# USB_Codec.net
KiCad netlist of a schematic drawn in EAGLE
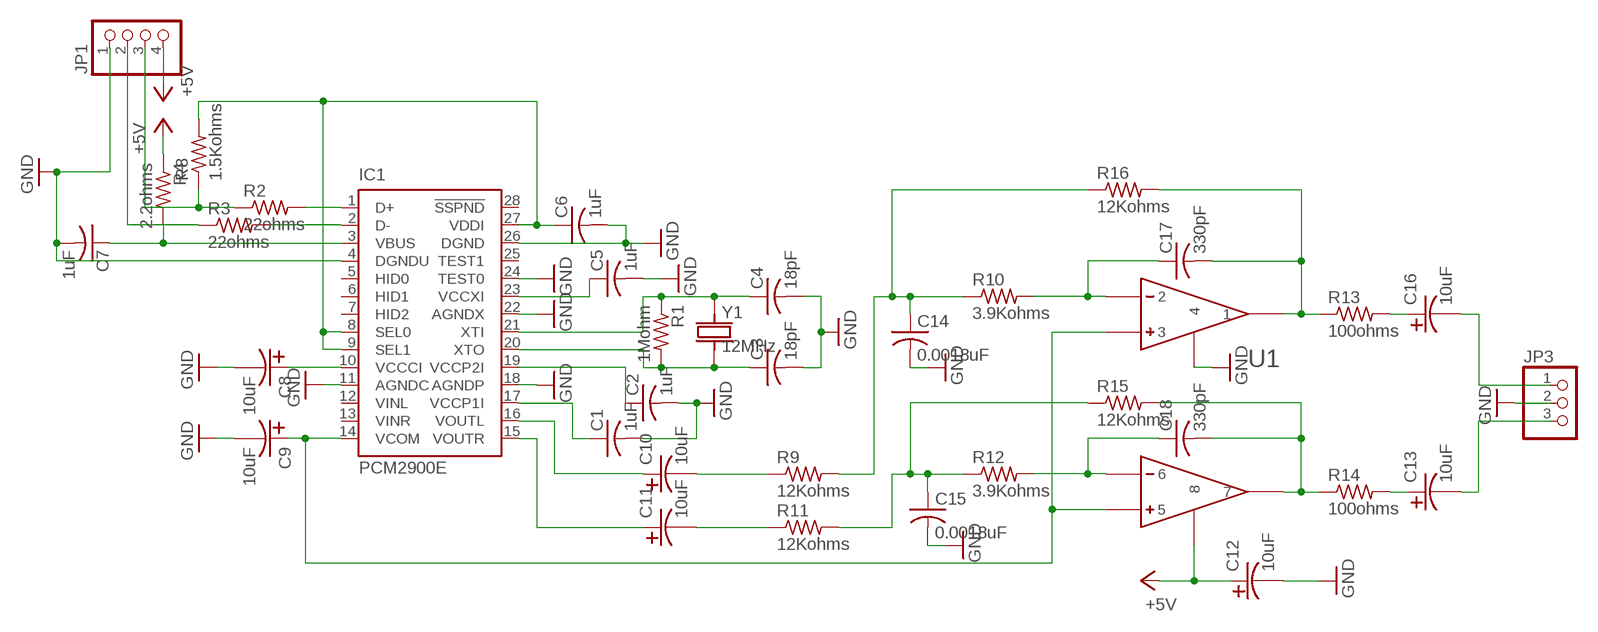
[diagram p0: schematic, sheet 1]

(export (version "E")
  (design (tool "Eeschema 10.0.6"))
  (components
    (comp (ref "C1")
      (value "1uF")
      (footprint "eagle-import:0603_CAP")
      (libsource (lib "eagle-import") (part "CAP0603"))
    )
    (comp (ref "C2")
      (value "1uF")
      (footprint "eagle-import:0603_CAP")
      (libsource (lib "eagle-import") (part "CAP0603"))
    )
    (comp (ref "C3")
      (value "18pF")
      (footprint "eagle-import:0603_CAP")
      (libsource (lib "eagle-import") (part "CAP0603"))
    )
    (comp (ref "C4")
      (value "18pF")
      (footprint "eagle-import:0603_CAP")
      (libsource (lib "eagle-import") (part "CAP0603"))
    )
    (comp (ref "C5")
      (value "1uF")
      (footprint "eagle-import:0603_CAP")
      (libsource (lib "eagle-import") (part "CAP0603"))
    )
    (comp (ref "C6")
      (value "1uF")
      (footprint "eagle-import:0603_CAP")
      (libsource (lib "eagle-import") (part "CAP0603"))
    )
    (comp (ref "C7")
      (value "1uF")
      (footprint "eagle-import:0603_CAP")
      (libsource (lib "eagle-import") (part "CAP0603"))
    )
    (comp (ref "C8")
      (value "10uF")
      (footprint "eagle-import:1411_CAP")
      (libsource (lib "eagle-import") (part "CAP-TANT"))
    )
    (comp (ref "C9")
      (value "10uF")
      (footprint "eagle-import:1411_CAP")
      (libsource (lib "eagle-import") (part "CAP-TANT"))
    )
    (comp (ref "C10")
      (value "10uF")
      (footprint "eagle-import:1411_CAP")
      (libsource (lib "eagle-import") (part "CAP-TANT"))
    )
    (comp (ref "C11")
      (value "10uF")
      (footprint "eagle-import:1411_CAP")
      (libsource (lib "eagle-import") (part "CAP-TANT"))
    )
    (comp (ref "C12")
      (value "10uF")
      (footprint "eagle-import:1411_CAP")
      (libsource (lib "eagle-import") (part "CAP-TANT"))
    )
    (comp (ref "C13")
      (value "10uF")
      (footprint "eagle-import:1411_CAP")
      (libsource (lib "eagle-import") (part "CAP-TANT"))
    )
    (comp (ref "C14")
      (value "0.0018uF")
      (footprint "eagle-import:0603_CAP")
      (libsource (lib "eagle-import") (part "CAP0603"))
    )
    (comp (ref "C15")
      (value "0.0018uF")
      (footprint "eagle-import:0603_CAP")
      (libsource (lib "eagle-import") (part "CAP0603"))
    )
    (comp (ref "C16")
      (value "10uF")
      (footprint "eagle-import:1411_CAP")
      (libsource (lib "eagle-import") (part "CAP-TANT"))
    )
    (comp (ref "C17")
      (value "330pF")
      (footprint "eagle-import:0603_CAP")
      (libsource (lib "eagle-import") (part "CAP0603"))
    )
    (comp (ref "C18")
      (value "330pF")
      (footprint "eagle-import:0603_CAP")
      (libsource (lib "eagle-import") (part "CAP0603"))
    )
    (comp (ref "IC1")
      (value "PCM2900E")
      (footprint "eagle-import:SSOP28DB")
      (fields (field (name "MF") "TEXAS INSTRUMENTS"))
      (libsource (lib "eagle-import") (part "PCM2900E"))
    )
    (comp (ref "JP1")
      (value "PINHD-1X4")
      (footprint "eagle-import:1X04")
      (libsource (lib "eagle-import") (part "PINHD-1X4"))
    )
    (comp (ref "JP3")
      (value "PINHD-1X3")
      (footprint "eagle-import:1X03")
      (libsource (lib "eagle-import") (part "PINHD-1X3"))
    )
    (comp (ref "R1")
      (value "1Mohm")
      (footprint "eagle-import:0603_RESISTOR")
      (libsource (lib "eagle-import") (part "RESISTOR0603"))
    )
    (comp (ref "R2")
      (value "22ohms")
      (footprint "eagle-import:0603_RESISTOR")
      (libsource (lib "eagle-import") (part "RESISTOR0603"))
    )
    (comp (ref "R3")
      (value "22ohms")
      (footprint "eagle-import:0603_RESISTOR")
      (libsource (lib "eagle-import") (part "RESISTOR0603"))
    )
    (comp (ref "R4")
      (value "2.2ohms")
      (footprint "eagle-import:0603_RESISTOR")
      (libsource (lib "eagle-import") (part "RESISTOR0603"))
    )
    (comp (ref "R8")
      (value "1.5Kohms")
      (footprint "eagle-import:0603_RESISTOR")
      (libsource (lib "eagle-import") (part "RESISTOR0603"))
    )
    (comp (ref "R9")
      (value "12Kohms")
      (footprint "eagle-import:0603_RESISTOR")
      (libsource (lib "eagle-import") (part "RESISTOR0603"))
    )
    (comp (ref "R10")
      (value "3.9Kohms")
      (footprint "eagle-import:0603_RESISTOR")
      (libsource (lib "eagle-import") (part "RESISTOR0603"))
    )
    (comp (ref "R11")
      (value "12Kohms")
      (footprint "eagle-import:0603_RESISTOR")
      (libsource (lib "eagle-import") (part "RESISTOR0603"))
    )
    (comp (ref "R12")
      (value "3.9Kohms")
      (footprint "eagle-import:0603_RESISTOR")
      (libsource (lib "eagle-import") (part "RESISTOR0603"))
    )
    (comp (ref "R13")
      (value "100ohms")
      (footprint "eagle-import:0603_RESISTOR")
      (libsource (lib "eagle-import") (part "RESISTOR0603"))
    )
    (comp (ref "R14")
      (value "100ohms")
      (footprint "eagle-import:0603_RESISTOR")
      (libsource (lib "eagle-import") (part "RESISTOR0603"))
    )
    (comp (ref "R15")
      (value "12Kohms")
      (footprint "eagle-import:0603_RESISTOR")
      (libsource (lib "eagle-import") (part "RESISTOR0603"))
    )
    (comp (ref "R16")
      (value "12Kohms")
      (footprint "eagle-import:0603_RESISTOR")
      (libsource (lib "eagle-import") (part "RESISTOR0603"))
    )
    (comp (ref "U1")
      (value "OP-AMP")
      (footprint "eagle-import:OPA2353UA")
      (libsource (lib "eagle-import") (part "OP-AMP"))
    )
    (comp (ref "Y1")
      (value "12MHz")
      (footprint "eagle-import:CRYSTAL_5X3")
      (libsource (lib "eagle-import") (part "CRYSTAL5X3"))
    )
  )
  (nets
    (net (code "1") (name "+5V") (class "Default")
      (node (ref "C12") (pin "P$1") (pinfunction "P$1_P$1") (pintype "passive"))
      (node (ref "JP1") (pin "4") (pinfunction "4_4") (pintype "passive"))
      (node (ref "R4") (pin "1") (pinfunction "1_1") (pintype "passive"))
      (node (ref "U1") (pin "P$8") (pinfunction "8_P$8") (pintype "bidirectional"))
    )
    (net (code "2") (name "GND") (class "Default")
      (node (ref "C1") (pin "2") (pinfunction "2_2") (pintype "passive"))
      (node (ref "C12") (pin "P$2") (pinfunction "P$2_P$2") (pintype "passive"))
      (node (ref "C14") (pin "2") (pinfunction "2_2") (pintype "passive"))
      (node (ref "C15") (pin "2") (pinfunction "2_2") (pintype "passive"))
      (node (ref "C2") (pin "2") (pinfunction "2_2") (pintype "passive"))
      (node (ref "C3") (pin "2") (pinfunction "2_2") (pintype "passive"))
      (node (ref "C4") (pin "2") (pinfunction "2_2") (pintype "passive"))
      (node (ref "C5") (pin "2") (pinfunction "2_2") (pintype "passive"))
      (node (ref "C6") (pin "2") (pinfunction "2_2") (pintype "passive"))
      (node (ref "C7") (pin "2") (pinfunction "2_2") (pintype "passive"))
      (node (ref "C8") (pin "P$2") (pinfunction "P$2_P$2") (pintype "passive"))
      (node (ref "C9") (pin "P$2") (pinfunction "P$2_P$2") (pintype "passive"))
      (node (ref "IC1") (pin "11") (pinfunction "AGNDC_11") (pintype "power_in"))
      (node (ref "IC1") (pin "18") (pinfunction "AGNDP_18") (pintype "power_in"))
      (node (ref "IC1") (pin "22") (pinfunction "AGNDX_22") (pintype "power_in"))
      (node (ref "IC1") (pin "24") (pinfunction "TEST0_24") (pintype "input"))
      (node (ref "IC1") (pin "26") (pinfunction "DGND_26") (pintype "power_in"))
      (node (ref "IC1") (pin "4") (pinfunction "DGNDU_4") (pintype "power_in"))
      (node (ref "JP1") (pin "1") (pinfunction "1_1") (pintype "passive"))
      (node (ref "JP3") (pin "2") (pinfunction "2_2") (pintype "passive"))
      (node (ref "U1") (pin "P$4") (pinfunction "4_P$4") (pintype "bidirectional"))
    )
    (net (code "3") (name "Net-(C10-PadP$2)") (class "Default")
      (node (ref "C10") (pin "P$2") (pinfunction "P$2_P$2") (pintype "passive"))
      (node (ref "R9") (pin "1") (pinfunction "1_1") (pintype "passive"))
    )
    (net (code "4") (name "Net-(C11-PadP$2)") (class "Default")
      (node (ref "C11") (pin "P$2") (pinfunction "P$2_P$2") (pintype "passive"))
      (node (ref "R11") (pin "1") (pinfunction "1_1") (pintype "passive"))
    )
    (net (code "5") (name "Net-(C13-PadP$1)") (class "Default")
      (node (ref "C13") (pin "P$1") (pinfunction "P$1_P$1") (pintype "passive"))
      (node (ref "R14") (pin "2") (pinfunction "2_2") (pintype "passive"))
    )
    (net (code "6") (name "Net-(C13-PadP$2)") (class "Default")
      (node (ref "C13") (pin "P$2") (pinfunction "P$2_P$2") (pintype "passive"))
      (node (ref "JP3") (pin "3") (pinfunction "3_3") (pintype "passive"))
    )
    (net (code "7") (name "Net-(C14-Pad1)") (class "Default")
      (node (ref "C14") (pin "1") (pinfunction "1_1") (pintype "passive"))
      (node (ref "R10") (pin "1") (pinfunction "1_1") (pintype "passive"))
      (node (ref "R16") (pin "1") (pinfunction "1_1") (pintype "passive"))
      (node (ref "R9") (pin "2") (pinfunction "2_2") (pintype "passive"))
    )
    (net (code "8") (name "Net-(C15-Pad1)") (class "Default")
      (node (ref "C15") (pin "1") (pinfunction "1_1") (pintype "passive"))
      (node (ref "R11") (pin "2") (pinfunction "2_2") (pintype "passive"))
      (node (ref "R12") (pin "1") (pinfunction "1_1") (pintype "passive"))
      (node (ref "R15") (pin "1") (pinfunction "1_1") (pintype "passive"))
    )
    (net (code "9") (name "Net-(C16-PadP$1)") (class "Default")
      (node (ref "C16") (pin "P$1") (pinfunction "P$1_P$1") (pintype "passive"))
      (node (ref "R13") (pin "2") (pinfunction "2_2") (pintype "passive"))
    )
    (net (code "10") (name "Net-(C16-PadP$2)") (class "Default")
      (node (ref "C16") (pin "P$2") (pinfunction "P$2_P$2") (pintype "passive"))
      (node (ref "JP3") (pin "1") (pinfunction "1_1") (pintype "passive"))
    )
    (net (code "11") (name "Net-(IC1-D+)") (class "Default")
      (node (ref "IC1") (pin "1") (pinfunction "D+_1") (pintype "bidirectional"))
      (node (ref "R2") (pin "2") (pinfunction "2_2") (pintype "passive"))
    )
    (net (code "12") (name "Net-(IC1-D-)") (class "Default")
      (node (ref "IC1") (pin "2") (pinfunction "D-_2") (pintype "bidirectional"))
      (node (ref "R3") (pin "2") (pinfunction "2_2") (pintype "passive"))
    )
    (net (code "13") (name "Net-(IC1-SEL0)") (class "Default")
      (node (ref "C6") (pin "1") (pinfunction "1_1") (pintype "passive"))
      (node (ref "IC1") (pin "27") (pinfunction "VDDI_27") (pintype "power_in"))
      (node (ref "IC1") (pin "8") (pinfunction "SEL0_8") (pintype "input"))
      (node (ref "IC1") (pin "9") (pinfunction "SEL1_9") (pintype "input"))
      (node (ref "R8") (pin "2") (pinfunction "2_2") (pintype "passive"))
    )
    (net (code "14") (name "Net-(IC1-VBUS)") (class "Default")
      (node (ref "C7") (pin "1") (pinfunction "1_1") (pintype "passive"))
      (node (ref "IC1") (pin "3") (pinfunction "VBUS_3") (pintype "power_in"))
      (node (ref "R4") (pin "2") (pinfunction "2_2") (pintype "passive"))
    )
    (net (code "15") (name "Net-(IC1-VCCCI)") (class "Default")
      (node (ref "C8") (pin "P$1") (pinfunction "P$1_P$1") (pintype "passive"))
      (node (ref "IC1") (pin "10") (pinfunction "VCCCI_10") (pintype "power_in"))
    )
    (net (code "16") (name "Net-(IC1-VCCP1I)") (class "Default")
      (node (ref "C1") (pin "1") (pinfunction "1_1") (pintype "passive"))
      (node (ref "IC1") (pin "17") (pinfunction "VCCP1I_17") (pintype "input"))
    )
    (net (code "17") (name "Net-(IC1-VCCP2I)") (class "Default")
      (node (ref "C2") (pin "1") (pinfunction "1_1") (pintype "passive"))
      (node (ref "IC1") (pin "19") (pinfunction "VCCP2I_19") (pintype "power_in"))
    )
    (net (code "18") (name "Net-(IC1-VCCXI)") (class "Default")
      (node (ref "C5") (pin "1") (pinfunction "1_1") (pintype "passive"))
      (node (ref "IC1") (pin "23") (pinfunction "VCCXI_23") (pintype "power_in"))
    )
    (net (code "19") (name "Net-(IC1-VCOM)") (class "Default")
      (node (ref "C9") (pin "P$1") (pinfunction "P$1_P$1") (pintype "passive"))
      (node (ref "IC1") (pin "14") (pinfunction "VCOM_14") (pintype "power_in"))
      (node (ref "U1") (pin "P$3") (pinfunction "3_P$3") (pintype "bidirectional"))
      (node (ref "U1") (pin "P$5") (pinfunction "5_P$5") (pintype "bidirectional"))
    )
    (net (code "20") (name "Net-(IC1-VOUTL)") (class "Default")
      (node (ref "C10") (pin "P$1") (pinfunction "P$1_P$1") (pintype "passive"))
      (node (ref "IC1") (pin "16") (pinfunction "VOUTL_16") (pintype "output"))
    )
    (net (code "21") (name "Net-(IC1-VOUTR)") (class "Default")
      (node (ref "C11") (pin "P$1") (pinfunction "P$1_P$1") (pintype "passive"))
      (node (ref "IC1") (pin "15") (pinfunction "VOUTR_15") (pintype "output"))
    )
    (net (code "22") (name "Net-(IC1-XTI)") (class "Default")
      (node (ref "C4") (pin "1") (pinfunction "1_1") (pintype "passive"))
      (node (ref "IC1") (pin "21") (pinfunction "XTI_21") (pintype "input"))
      (node (ref "R1") (pin "1") (pinfunction "1_1") (pintype "passive"))
      (node (ref "Y1") (pin "1") (pinfunction "1_1") (pintype "passive"))
    )
    (net (code "23") (name "Net-(IC1-XTO)") (class "Default")
      (node (ref "C3") (pin "1") (pinfunction "1_1") (pintype "passive"))
      (node (ref "IC1") (pin "20") (pinfunction "XTO_20") (pintype "output"))
      (node (ref "R1") (pin "2") (pinfunction "2_2") (pintype "passive"))
      (node (ref "Y1") (pin "2") (pinfunction "2_2") (pintype "passive"))
    )
    (net (code "24") (name "Net-(JP1-Pad2)") (class "Default")
      (node (ref "JP1") (pin "2") (pinfunction "2_2") (pintype "passive"))
      (node (ref "R3") (pin "1") (pinfunction "1_1") (pintype "passive"))
    )
    (net (code "25") (name "Net-(JP1-Pad3)") (class "Default")
      (node (ref "JP1") (pin "3") (pinfunction "3_3") (pintype "passive"))
      (node (ref "R2") (pin "1") (pinfunction "1_1") (pintype "passive"))
      (node (ref "R8") (pin "1") (pinfunction "1_1") (pintype "passive"))
    )
    (net (code "26") (name "Net-(U1-1)") (class "Default")
      (node (ref "C17") (pin "2") (pinfunction "2_2") (pintype "passive"))
      (node (ref "R13") (pin "1") (pinfunction "1_1") (pintype "passive"))
      (node (ref "R16") (pin "2") (pinfunction "2_2") (pintype "passive"))
      (node (ref "U1") (pin "P$1") (pinfunction "1_P$1") (pintype "bidirectional"))
    )
    (net (code "27") (name "Net-(U1-2)") (class "Default")
      (node (ref "C17") (pin "1") (pinfunction "1_1") (pintype "passive"))
      (node (ref "R10") (pin "2") (pinfunction "2_2") (pintype "passive"))
      (node (ref "U1") (pin "P$2") (pinfunction "2_P$2") (pintype "bidirectional"))
    )
    (net (code "28") (name "Net-(U1-6)") (class "Default")
      (node (ref "C18") (pin "1") (pinfunction "1_1") (pintype "passive"))
      (node (ref "R12") (pin "2") (pinfunction "2_2") (pintype "passive"))
      (node (ref "U1") (pin "P$6") (pinfunction "6_P$6") (pintype "bidirectional"))
    )
    (net (code "29") (name "Net-(U1-7)") (class "Default")
      (node (ref "C18") (pin "2") (pinfunction "2_2") (pintype "passive"))
      (node (ref "R14") (pin "1") (pinfunction "1_1") (pintype "passive"))
      (node (ref "R15") (pin "2") (pinfunction "2_2") (pintype "passive"))
      (node (ref "U1") (pin "P$7") (pinfunction "7_P$7") (pintype "bidirectional"))
    )
    (net (code "30") (name "unconnected-(IC1-HID0-Pad5)") (class "Default")
      (node (ref "IC1") (pin "5") (pinfunction "HID0_5") (pintype "input"))
    )
    (net (code "31") (name "unconnected-(IC1-HID1-Pad6)") (class "Default")
      (node (ref "IC1") (pin "6") (pinfunction "HID1_6") (pintype "input"))
    )
    (net (code "32") (name "unconnected-(IC1-HID2-Pad7)") (class "Default")
      (node (ref "IC1") (pin "7") (pinfunction "HID2_7") (pintype "input"))
    )
    (net (code "33") (name "unconnected-(IC1-TEST1-Pad25)") (class "Default")
      (node (ref "IC1") (pin "25") (pinfunction "TEST1_25") (pintype "output"))
    )
    (net (code "34") (name "unconnected-(IC1-VINL-Pad12)") (class "Default")
      (node (ref "IC1") (pin "12") (pinfunction "VINL_12") (pintype "input"))
    )
    (net (code "35") (name "unconnected-(IC1-VINR-Pad13)") (class "Default")
      (node (ref "IC1") (pin "13") (pinfunction "VINR_13") (pintype "input"))
    )
    (net (code "36") (name "unconnected-(IC1-~{SSPND}-Pad28)") (class "Default")
      (node (ref "IC1") (pin "28") (pinfunction "~{SSPND}_28") (pintype "output"))
    )
  )
)
